# PN532.net
KiCad netlist of a schematic drawn in Altium Designer
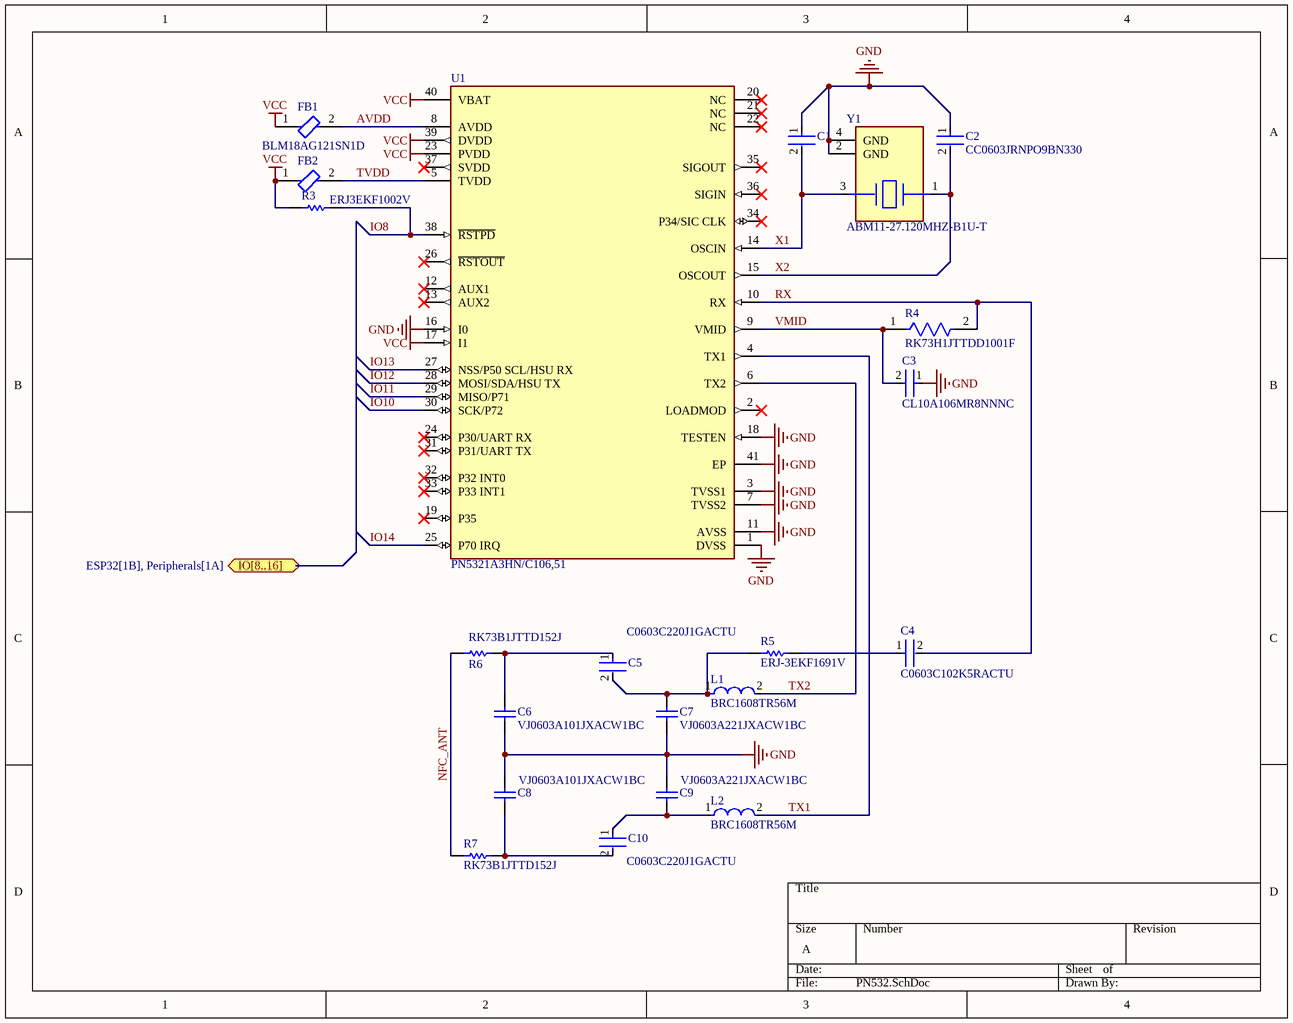
[diagram p0: PN532.SchDoc]

(export (version "E")
  (design (tool "Eeschema 10.0.6"))
  (components
    (comp (ref "C1")
      (value "CC0603JRNPO9BN330")
      (footprint "FP-CC0603-0_9-IPC_C")
      (description "CAP CER 33PF 50V C0G/NPO 0603")
      (fields (field (name "TOLERANCE") "5%") (field (name "VOLTAGE") "50V"))
      (libsource (lib "Altium Content Vault") (part "b4654b650e69147ec39a6b967a45e02"))
    )
    (comp (ref "C2")
      (value "CC0603JRNPO9BN330")
      (footprint "FP-CC0603-0_9-IPC_C")
      (description "CAP CER 33PF 50V C0G/NPO 0603")
      (fields (field (name "TOLERANCE") "5%") (field (name "VOLTAGE") "50V"))
      (libsource (lib "Altium Content Vault") (part "b4654b650e69147ec39a6b967a45e02"))
    )
    (comp (ref "C3")
      (value "CL10A106MR8NNNC")
      (footprint "FP-CL10-IPC_C")
      (description "Cap Ceramic 10uF 4V X5R ±20% Pad SMD 0603 +85°C T/R")
      (fields (field (name "TOLERANCE") "20%"))
      (libsource (lib "Altium Content Vault") (part "b4654b650e69147ec39a6b967a45e02"))
    )
    (comp (ref "C4")
      (value "C0603C102K5RACTU")
      (footprint "FP-C0603C-CF-MFG")
      (description "CAP CER 1000PF 50V X7R 0603")
      (fields
        (field (name "TOLERANCE") "0.1")
        (field (name "OCTOPART") "https://octopart.com/c0603c102k5ractu-kemet-144878")
      )
      (libsource (lib "Altium Content Vault") (part "b4654b650e69147ec39a6b967a45e02"))
    )
    (comp (ref "C5")
      (value "C0603C220J1GACTU")
      (footprint "FP-C0603C-CF-MFG")
      (description "CAP CER 22PF 100V 5% NP0 0603")
      (fields (field (name "MANUFACTURER") "KEMET") (field (name "TOLERANCE") "0.05"))
      (libsource (lib "Altium Content Vault") (part "b4654b650e69147ec39a6b967a45e02"))
    )
    (comp (ref "C6")
      (value "VJ0603A101JXACW1BC")
      (footprint "CAPC1608X95X40ML15T15")
      (fields (field (name "MANUFACTURER") "Vitramon"))
      (libsource (lib "Altium Content Vault") (part "CAP"))
    )
    (comp (ref "C7")
      (value "VJ0603A221JXACW1BC")
      (footprint "CAPC1608X95X40ML15T15")
      (fields (field (name "MANUFACTURER") "Vitramon"))
      (libsource (lib "Altium Content Vault") (part "CAP"))
    )
    (comp (ref "C8")
      (value "VJ0603A101JXACW1BC")
      (footprint "CAPC1608X95X40ML15T15")
      (fields (field (name "MANUFACTURER") "Vitramon"))
      (libsource (lib "Altium Content Vault") (part "CAP"))
    )
    (comp (ref "C9")
      (value "VJ0603A221JXACW1BC")
      (footprint "CAPC1608X95X40ML15T15")
      (fields (field (name "MANUFACTURER") "Vitramon"))
      (libsource (lib "Altium Content Vault") (part "CAP"))
    )
    (comp (ref "C10")
      (value "C0603C220J1GACTU")
      (footprint "FP-C0603C-CF-MFG")
      (description "CAP CER 22PF 100V 5% NP0 0603")
      (fields (field (name "MANUFACTURER") "KEMET") (field (name "TOLERANCE") "0.05"))
      (libsource (lib "Altium Content Vault") (part "b4654b650e69147ec39a6b967a45e02"))
    )
    (comp (ref "FB1")
      (value "BLM18AG121SN1D")
      (footprint "FP-BLM18-0_15-t0_8-IPC_B")
      (description "Chip Ferrite Bead, 0603, 120Ω @ 100MHz, 0.18Ω, 25%, 800mA")
      (fields (field (name "TOLERANCE") "25%"))
      (libsource (lib "Altium Content Vault") (part "5f30dd21d616792df468990f7003faa"))
    )
    (comp (ref "FB2")
      (value "BLM18AG121SN1D")
      (footprint "FP-BLM18-0_15-t0_8-IPC_B")
      (description "Chip Ferrite Bead, 0603, 120Ω @ 100MHz, 0.18Ω, 25%, 800mA")
      (fields (field (name "TOLERANCE") "25%"))
      (libsource (lib "Altium Content Vault") (part "5f30dd21d616792df468990f7003faa"))
    )
    (comp (ref "L1")
      (value "BRC1608TR56M")
      (footprint "FP-BRC1608-MFG")
      (description "FIXED IND 560NH 760MA 95 MOHM")
      (fields (field (name "TOLERANCE") "20%"))
      (libsource (lib "Altium Content Vault") (part "725321dda6339637d4d059423bc1c3c"))
    )
    (comp (ref "L2")
      (value "BRC1608TR56M")
      (footprint "FP-BRC1608-MFG")
      (description "FIXED IND 560NH 760MA 95 MOHM")
      (fields (field (name "TOLERANCE") "20%"))
      (libsource (lib "Altium Content Vault") (part "725321dda6339637d4d059423bc1c3c"))
    )
    (comp (ref "R3")
      (value "ERJ3EKF1002V")
      (footprint "RESC1609X55X30LL15T15")
      (description "Chip Resistor, 10 KOhm, +/- 1%, 0.1 W, -55 to 155 degC, 0603 (1608 Metric), RoHS, Tape and Reel")
      (fields (field (name "TOLERANCE") "1%") (field (name "MANUFACTURER") "Panasonic"))
      (libsource (lib "Altium Content Vault") (part "RES-2"))
    )
    (comp (ref "R4")
      (value "RK73H1JTTDD1001F")
      (footprint "FP-RK73H1J-IPC_A")
      (description "1kΩ ±1% 0.125W Chip Resistor 0603 Thick Film AEC-Q200 Qualified")
      (fields (field (name "TOLERANCE") "1%"))
      (libsource (lib "Altium Content Vault") (part "1029c3af85768c4190bb7ad29bc67b5"))
    )
    (comp (ref "R5")
      (value "ERJ-3EKF1691V")
      (footprint "RESC1608X55X30NL15T15")
      (fields (field (name "MANUFACTURER") "Panasonic"))
      (libsource (lib "Altium Content Vault") (part "RES"))
    )
    (comp (ref "R6")
      (value "RK73B1JTTD152J")
      (footprint "RESC1608X55X30LL20T10")
      (fields (field (name "MANUFACTURER") "KOA Speer"))
      (libsource (lib "Altium Content Vault") (part "RES"))
    )
    (comp (ref "R7")
      (value "RK73B1JTTD152J")
      (footprint "RESC1608X55X30LL20T10")
      (fields (field (name "MANUFACTURER") "KOA Speer"))
      (libsource (lib "Altium Content Vault") (part "RES"))
    )
    (comp (ref "U1")
      (value "PN5321A3HN/C106,51")
      (footprint "FP-SOT618-1-MFG")
      (description "IC RFID RDR/TRAN 13.56MZ 40HVQFN")
      (fields
        (field (name "OCTOPART") "https://octopart.com/pn5321a3hn%2Fc106%2C51-nxp+semiconductors-18453768")
        (field (name "MANUFACTURER") "NXP Semiconductors")
      )
      (libsource (lib "Altium Content Vault") (part "86bf4db31c09736a9dec32adae5c84e"))
    )
    (comp (ref "Y1")
      (value "ABM11-27.120MHZ-B1U-T")
      (footprint "FP-ABM11-MFG")
      (description "Crystal 27.12MHz ±10ppm 10pF SMD-4 2mm x 1.6mm")
      (libsource (lib "Altium Content Vault") (part "b3c1237d77310e73098bcf11eecb25f"))
    )
  )
  (nets
    (net (code "4") (name "/AVDD") (class "Default")
      (node (ref "FB1") (pin "2") (pinfunction "2_2") (pintype "passive"))
      (node (ref "U1") (pin "8") (pinfunction "AVDD_8") (pintype "power_in"))
    )
    (net (code "5") (name "/IO8") (class "Default")
      (node (ref "R3") (pin "1") (pinfunction "1_1") (pintype "passive"))
      (node (ref "U1") (pin "38") (pinfunction "~{RSTPD}_38") (pintype "input"))
    )
    (net (code "6") (name "/IO10") (class "Default")
      (node (ref "U1") (pin "30") (pinfunction "SCK/P72_30") (pintype "bidirectional"))
    )
    (net (code "7") (name "/IO11") (class "Default")
      (node (ref "U1") (pin "29") (pinfunction "MISO/P71_29") (pintype "bidirectional"))
    )
    (net (code "8") (name "/IO12") (class "Default")
      (node (ref "U1") (pin "28") (pinfunction "MOSI/SDA/HSU_TX_28") (pintype "bidirectional"))
    )
    (net (code "9") (name "/IO13") (class "Default")
      (node (ref "U1") (pin "27") (pinfunction "NSS/P50_SCL/HSU_RX_27") (pintype "bidirectional"))
    )
    (net (code "10") (name "/IO14") (class "Default")
      (node (ref "U1") (pin "25") (pinfunction "P70_IRQ_25") (pintype "bidirectional"))
    )
    (net (code "12") (name "/NFC_ANT") (class "Default")
      (node (ref "R6") (pin "1") (pinfunction "1_1") (pintype "passive"))
      (node (ref "R7") (pin "1") (pinfunction "1_1") (pintype "passive"))
    )
    (net (code "13") (name "/RX") (class "Default")
      (node (ref "C4") (pin "2") (pinfunction "2_2") (pintype "passive"))
      (node (ref "R4") (pin "2") (pinfunction "2_2") (pintype "passive"))
      (node (ref "U1") (pin "10") (pinfunction "RX_10") (pintype "input"))
    )
    (net (code "14") (name "/TVDD") (class "Default")
      (node (ref "FB2") (pin "2") (pinfunction "2_2") (pintype "passive"))
      (node (ref "U1") (pin "5") (pinfunction "TVDD_5") (pintype "power_in"))
    )
    (net (code "15") (name "/TX1") (class "Default")
      (node (ref "L2") (pin "2") (pinfunction "2_2") (pintype "passive"))
      (node (ref "U1") (pin "4") (pinfunction "TX1_4") (pintype "output"))
    )
    (net (code "16") (name "/TX2") (class "Default")
      (node (ref "L1") (pin "2") (pinfunction "2_2") (pintype "passive"))
      (node (ref "U1") (pin "6") (pinfunction "TX2_6") (pintype "output"))
    )
    (net (code "17") (name "/VMID") (class "Default")
      (node (ref "C3") (pin "2") (pinfunction "2_2") (pintype "passive"))
      (node (ref "R4") (pin "1") (pinfunction "1_1") (pintype "passive"))
      (node (ref "U1") (pin "9") (pinfunction "VMID_9") (pintype "output"))
    )
    (net (code "18") (name "/X1") (class "Default")
      (node (ref "C1") (pin "2") (pinfunction "2_2") (pintype "passive"))
      (node (ref "U1") (pin "14") (pinfunction "OSCIN_14") (pintype "input"))
      (node (ref "Y1") (pin "3") (pinfunction "3_3") (pintype "passive"))
    )
    (net (code "19") (name "/X2") (class "Default")
      (node (ref "C2") (pin "2") (pinfunction "2_2") (pintype "passive"))
      (node (ref "U1") (pin "15") (pinfunction "OSCOUT_15") (pintype "output"))
      (node (ref "Y1") (pin "1") (pinfunction "1_1") (pintype "passive"))
    )
    (net (code "20") (name "GND") (class "Default")
      (node (ref "C1") (pin "1") (pinfunction "1_1") (pintype "passive"))
      (node (ref "C2") (pin "1") (pinfunction "1_1") (pintype "passive"))
      (node (ref "C3") (pin "1") (pinfunction "1_1") (pintype "passive"))
      (node (ref "C6") (pin "1") (pinfunction "1_1") (pintype "passive"))
      (node (ref "C7") (pin "1") (pinfunction "1_1") (pintype "passive"))
      (node (ref "C8") (pin "2") (pinfunction "2_2") (pintype "passive"))
      (node (ref "C9") (pin "2") (pinfunction "2_2") (pintype "passive"))
      (node (ref "U1") (pin "1") (pinfunction "DVSS_1") (pintype "power_in"))
      (node (ref "U1") (pin "11") (pinfunction "AVSS_11") (pintype "power_in"))
      (node (ref "U1") (pin "16") (pinfunction "I0_16") (pintype "input"))
      (node (ref "U1") (pin "18") (pinfunction "TESTEN_18") (pintype "input"))
      (node (ref "U1") (pin "3") (pinfunction "TVSS1_3") (pintype "power_in"))
      (node (ref "U1") (pin "41") (pinfunction "EP_41") (pintype "passive"))
      (node (ref "U1") (pin "7") (pinfunction "TVSS2_7") (pintype "power_in"))
      (node (ref "Y1") (pin "2") (pinfunction "GND_2") (pintype "power_in"))
      (node (ref "Y1") (pin "4") (pinfunction "GND_4") (pintype "power_in"))
    )
    (net (code "21") (name "Net-(C4-Pad1)") (class "Default")
      (node (ref "C4") (pin "1") (pinfunction "1_1") (pintype "passive"))
      (node (ref "R5") (pin "1") (pinfunction "1_1") (pintype "passive"))
    )
    (net (code "22") (name "Net-(C5-Pad1)") (class "Default")
      (node (ref "C5") (pin "1") (pinfunction "1_1") (pintype "passive"))
      (node (ref "C6") (pin "2") (pinfunction "2_2") (pintype "passive"))
      (node (ref "R6") (pin "2") (pinfunction "2_2") (pintype "passive"))
    )
    (net (code "23") (name "Net-(C5-Pad2)") (class "Default")
      (node (ref "C5") (pin "2") (pinfunction "2_2") (pintype "passive"))
      (node (ref "C7") (pin "2") (pinfunction "2_2") (pintype "passive"))
      (node (ref "L1") (pin "1") (pinfunction "1_1") (pintype "passive"))
      (node (ref "R5") (pin "2") (pinfunction "2_2") (pintype "passive"))
    )
    (net (code "24") (name "Net-(C10-Pad1)") (class "Default")
      (node (ref "C10") (pin "1") (pinfunction "1_1") (pintype "passive"))
      (node (ref "C9") (pin "1") (pinfunction "1_1") (pintype "passive"))
      (node (ref "L2") (pin "1") (pinfunction "1_1") (pintype "passive"))
    )
    (net (code "25") (name "Net-(C10-Pad2)") (class "Default")
      (node (ref "C10") (pin "2") (pinfunction "2_2") (pintype "passive"))
      (node (ref "C8") (pin "1") (pinfunction "1_1") (pintype "passive"))
      (node (ref "R7") (pin "2") (pinfunction "2_2") (pintype "passive"))
    )
    (net (code "26") (name "VCC") (class "Default")
      (node (ref "FB1") (pin "1") (pinfunction "1_1") (pintype "passive"))
      (node (ref "FB2") (pin "1") (pinfunction "1_1") (pintype "passive"))
      (node (ref "R3") (pin "2") (pinfunction "2_2") (pintype "passive"))
      (node (ref "U1") (pin "17") (pinfunction "I1_17") (pintype "input"))
      (node (ref "U1") (pin "23") (pinfunction "PVDD_23") (pintype "power_in"))
      (node (ref "U1") (pin "39") (pinfunction "DVDD_39") (pintype "output"))
      (node (ref "U1") (pin "40") (pinfunction "VBAT_40") (pintype "power_in"))
    )
    (net (code "27") (name "unconnected-(U1-AUX1-Pad12)") (class "Default")
      (node (ref "U1") (pin "12") (pinfunction "AUX1_12") (pintype "output+no_connect"))
    )
    (net (code "28") (name "unconnected-(U1-AUX2-Pad13)") (class "Default")
      (node (ref "U1") (pin "13") (pinfunction "AUX2_13") (pintype "output+no_connect"))
    )
    (net (code "29") (name "unconnected-(U1-LOADMOD-Pad2)") (class "Default")
      (node (ref "U1") (pin "2") (pinfunction "LOADMOD_2") (pintype "output+no_connect"))
    )
    (net (code "30") (name "unconnected-(U1-NC-Pad20)") (class "Default")
      (node (ref "U1") (pin "20") (pinfunction "NC_20") (pintype "passive+no_connect"))
    )
    (net (code "31") (name "unconnected-(U1-NC-Pad21)") (class "Default")
      (node (ref "U1") (pin "21") (pinfunction "NC_21") (pintype "passive+no_connect"))
    )
    (net (code "32") (name "unconnected-(U1-NC-Pad22)") (class "Default")
      (node (ref "U1") (pin "22") (pinfunction "NC_22") (pintype "passive+no_connect"))
    )
    (net (code "33") (name "unconnected-(U1-P30{slash}UART_RX-Pad24)") (class "Default")
      (node (ref "U1") (pin "24") (pinfunction "P30/UART_RX_24") (pintype "bidirectional+no_connect"))
    )
    (net (code "34") (name "unconnected-(U1-P31{slash}UART_TX-Pad31)") (class "Default")
      (node (ref "U1") (pin "31") (pinfunction "P31/UART_TX_31") (pintype "bidirectional+no_connect"))
    )
    (net (code "35") (name "unconnected-(U1-P32_INT0-Pad32)") (class "Default")
      (node (ref "U1") (pin "32") (pinfunction "P32_INT0_32") (pintype "bidirectional+no_connect"))
    )
    (net (code "36") (name "unconnected-(U1-P33_INT1-Pad33)") (class "Default")
      (node (ref "U1") (pin "33") (pinfunction "P33_INT1_33") (pintype "bidirectional+no_connect"))
    )
    (net (code "37") (name "unconnected-(U1-P34{slash}SIC_CLK-Pad34)") (class "Default")
      (node (ref "U1") (pin "34") (pinfunction "P34/SIC_CLK_34") (pintype "bidirectional+no_connect"))
    )
    (net (code "38") (name "unconnected-(U1-P35-Pad19)") (class "Default")
      (node (ref "U1") (pin "19") (pinfunction "P35_19") (pintype "bidirectional+no_connect"))
    )
    (net (code "39") (name "unconnected-(U1-SIGIN-Pad36)") (class "Default")
      (node (ref "U1") (pin "36") (pinfunction "SIGIN_36") (pintype "input+no_connect"))
    )
    (net (code "40") (name "unconnected-(U1-SIGOUT-Pad35)") (class "Default")
      (node (ref "U1") (pin "35") (pinfunction "SIGOUT_35") (pintype "output+no_connect"))
    )
    (net (code "41") (name "unconnected-(U1-SVDD-Pad37)") (class "Default")
      (node (ref "U1") (pin "37") (pinfunction "SVDD_37") (pintype "output+no_connect"))
    )
    (net (code "42") (name "unconnected-(U1-~{RSTOUT}-Pad26)") (class "Default")
      (node (ref "U1") (pin "26") (pinfunction "~{RSTOUT}_26") (pintype "output+no_connect"))
    )
  )
)
